# ADC.net
KiCad netlist of a schematic drawn in Altium Designer
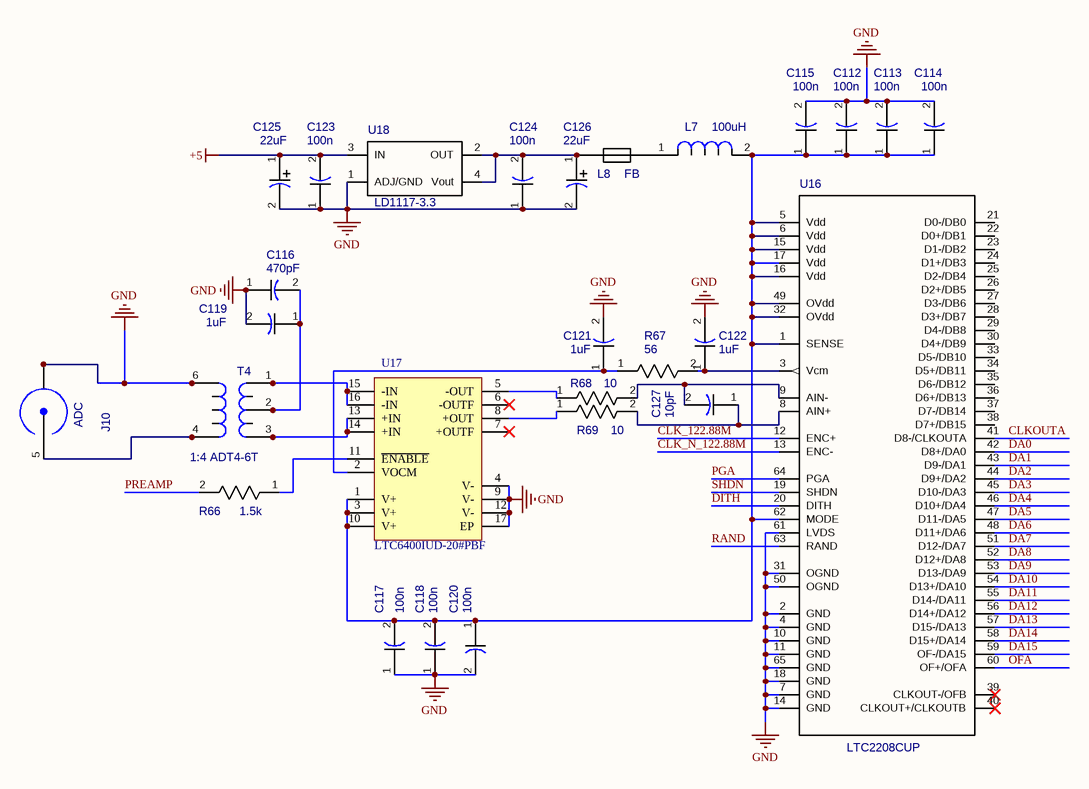
[diagram p0: ADC.SchDoc]

(export (version "E")
  (design (tool "Eeschema 10.0.6"))
  (components
    (comp (ref "C112")
      (value "100n")
      (footprint "CAP_0805")
      (description "CAP_0805")
      (libsource (lib "*") (part "CAP_0805"))
    )
    (comp (ref "C113")
      (value "100n")
      (footprint "CAP_0805")
      (description "CAP_0805")
      (libsource (lib "*") (part "CAP_0805"))
    )
    (comp (ref "C114")
      (value "100n")
      (footprint "CAP_0805")
      (description "CAP_0805")
      (libsource (lib "*") (part "CAP_0805"))
    )
    (comp (ref "C115")
      (value "100n")
      (footprint "CAP_0805")
      (description "CAP_0805")
      (libsource (lib "*") (part "CAP_0805"))
    )
    (comp (ref "C116")
      (value "470pF")
      (footprint "CAP_0805")
      (description "CAP_0805")
      (libsource (lib "*") (part "CAP_0805"))
    )
    (comp (ref "C117")
      (value "100n")
      (footprint "CAP_0805")
      (description "CAP_0805")
      (libsource (lib "*") (part "CAP_0805"))
    )
    (comp (ref "C118")
      (value "100n")
      (footprint "CAP_0805")
      (description "CAP_0805")
      (libsource (lib "*") (part "CAP_0805"))
    )
    (comp (ref "C119")
      (value "1uF")
      (footprint "CAP_0805")
      (description "CAP_0805")
      (libsource (lib "*") (part "CAP_0805"))
    )
    (comp (ref "C120")
      (value "100n")
      (footprint "CAP_0805")
      (description "CAP_0805")
      (libsource (lib "*") (part "CAP_0805"))
    )
    (comp (ref "C121")
      (value "1uF")
      (footprint "CAP_0805")
      (description "CAP_0805")
      (libsource (lib "*") (part "CAP_0805"))
    )
    (comp (ref "C122")
      (value "1uF")
      (footprint "CAP_0805")
      (description "CAP_0805")
      (libsource (lib "*") (part "CAP_0805"))
    )
    (comp (ref "C123")
      (value "100n")
      (footprint "CAP_0805")
      (description "CAP_0805")
      (libsource (lib "*") (part "CAP_0805"))
    )
    (comp (ref "C124")
      (value "100n")
      (footprint "CAP_0805")
      (description "CAP_0805")
      (libsource (lib "*") (part "CAP_0805"))
    )
    (comp (ref "C125") (value "22uF") (footprint "TC3528-1411") (libsource (lib "*") (part "EEEFC_sizeB")))
    (comp (ref "C126")
      (value "22uF")
      (footprint "TC3528-1411")
      (description "EEEFC_sizeB")
      (libsource (lib "*") (part "EEEFC_sizeB"))
    )
    (comp (ref "C127")
      (value "10pF")
      (footprint "CAP_0805")
      (description "CAP_0805")
      (libsource (lib "*") (part "CAP_0805"))
    )
    (comp (ref "J10")
      (value "ADC")
      (footprint "31-5431")
      (description "31-5431")
      (libsource (lib "RF-UNIT_1") (part "31-5431"))
    )
    (comp (ref "L7")
      (value "100uH")
      (footprint "14-1210")
      (description "IND_1206")
      (libsource (lib "*") (part "IND_1206"))
    )
    (comp (ref "L8")
      (value "FB")
      (footprint "IND_FERRITE_BEAD")
      (description "Ferrite bead on conductor")
      (libsource (lib "MOTHERBOARD_1") (part "IND_FERRITE_BEAD"))
    )
    (comp (ref "R66")
      (value "1.5k")
      (footprint "RES_0805")
      (description "RES_0805")
      (libsource (lib "*") (part "RES_0805"))
    )
    (comp (ref "R67")
      (value "56")
      (footprint "RES_0805")
      (description "RES_0805")
      (libsource (lib "") (part "RES_0805_1"))
    )
    (comp (ref "R68")
      (value "10")
      (footprint "RES_0603")
      (description "RES_0603")
      (libsource (lib "*") (part "RES_0603"))
    )
    (comp (ref "R69")
      (value "10")
      (footprint "RES_0603")
      (description "RES_0603")
      (libsource (lib "*") (part "RES_0603"))
    )
    (comp (ref "T4")
      (value "1:4 ADT4-6T")
      (footprint "TRANSF_ACORE2")
      (description "Transformer")
      (libsource (lib "MOTHERBOARD_1") (part "TRANSF_ACORE2"))
    )
    (comp (ref "U16") (value "LTC2208CUP") (footprint "LTC2208CUP") (libsource (lib "*") (part "LTC2208CUP")))
    (comp (ref "U17")
      (value "LTC6400IUD-20#PBF")
      (footprint "LT-UD-16_N")
      (fields
        (field (name "MANUFACTURER") "Linear Technology")
        (field (name "LINEAR TECHNOLOGY PART NUMBER") "LTC6400-20")
      )
      (libsource (lib "Altium Content Vault") (part "LT-LTC640X-X-16"))
    )
    (comp (ref "U18")
      (value "LD1117-3.3")
      (footprint "LT1117CST-3.3")
      (description "LT1117CST-3.3")
      (libsource (lib "*") (part "LT1117CST-3.3"))
    )
  )
  (nets
    (net (code "1") (name "+5") (class "Default")
      (node (ref "C123") (pin "2") (pinfunction "2_2") (pintype "passive"))
      (node (ref "C125") (pin "1") (pinfunction "PLUS_1") (pintype "passive"))
      (node (ref "U18") (pin "3") (pinfunction "IN_3") (pintype "passive"))
    )
    (net (code "2") (name "/CLKOUTA") (class "Default")
      (node (ref "U16") (pin "41") (pinfunction "D8-/CLKOUTA_41") (pintype "passive"))
    )
    (net (code "3") (name "/CLK_122.88M") (class "Default")
      (node (ref "U16") (pin "12") (pinfunction "ENC+_12") (pintype "passive"))
    )
    (net (code "4") (name "/CLK_N_122.88M") (class "Default")
      (node (ref "U16") (pin "13") (pinfunction "ENC-_13") (pintype "passive"))
    )
    (net (code "5") (name "/DA0") (class "Default")
      (node (ref "U16") (pin "42") (pinfunction "D8+/DA0_42") (pintype "passive"))
    )
    (net (code "6") (name "/DA1") (class "Default")
      (node (ref "U16") (pin "43") (pinfunction "D9-/DA1_43") (pintype "passive"))
    )
    (net (code "7") (name "/DA2") (class "Default")
      (node (ref "U16") (pin "44") (pinfunction "D9+/DA2_44") (pintype "passive"))
    )
    (net (code "8") (name "/DA3") (class "Default")
      (node (ref "U16") (pin "45") (pinfunction "D10-/DA3_45") (pintype "passive"))
    )
    (net (code "9") (name "/DA4") (class "Default")
      (node (ref "U16") (pin "46") (pinfunction "D10+/DA4_46") (pintype "passive"))
    )
    (net (code "10") (name "/DA5") (class "Default")
      (node (ref "U16") (pin "47") (pinfunction "D11-/DA5_47") (pintype "passive"))
    )
    (net (code "11") (name "/DA6") (class "Default")
      (node (ref "U16") (pin "48") (pinfunction "D11+/DA6_48") (pintype "passive"))
    )
    (net (code "12") (name "/DA7") (class "Default")
      (node (ref "U16") (pin "51") (pinfunction "D12-/DA7_51") (pintype "passive"))
    )
    (net (code "13") (name "/DA8") (class "Default")
      (node (ref "U16") (pin "52") (pinfunction "D12+/DA8_52") (pintype "passive"))
    )
    (net (code "14") (name "/DA9") (class "Default")
      (node (ref "U16") (pin "53") (pinfunction "D13-/DA9_53") (pintype "passive"))
    )
    (net (code "15") (name "/DA10") (class "Default")
      (node (ref "U16") (pin "54") (pinfunction "D13+/DA10_54") (pintype "passive"))
    )
    (net (code "16") (name "/DA11") (class "Default")
      (node (ref "U16") (pin "55") (pinfunction "D14-/DA11_55") (pintype "passive"))
    )
    (net (code "17") (name "/DA12") (class "Default")
      (node (ref "U16") (pin "56") (pinfunction "D14+/DA12_56") (pintype "passive"))
    )
    (net (code "18") (name "/DA13") (class "Default")
      (node (ref "U16") (pin "57") (pinfunction "D15-/DA13_57") (pintype "passive"))
    )
    (net (code "19") (name "/DA14") (class "Default")
      (node (ref "U16") (pin "58") (pinfunction "D15+/DA14_58") (pintype "passive"))
    )
    (net (code "20") (name "/DA15") (class "Default")
      (node (ref "U16") (pin "59") (pinfunction "OF-/DA15_59") (pintype "passive"))
    )
    (net (code "21") (name "/DITH") (class "Default")
      (node (ref "U16") (pin "20") (pinfunction "DITH_20") (pintype "passive"))
    )
    (net (code "22") (name "/OFA") (class "Default")
      (node (ref "U16") (pin "60") (pinfunction "OF+/OFA_60") (pintype "passive"))
    )
    (net (code "23") (name "/PGA") (class "Default")
      (node (ref "U16") (pin "64") (pinfunction "PGA_64") (pintype "passive"))
    )
    (net (code "24") (name "/PREAMP") (class "Default")
      (node (ref "R66") (pin "2") (pinfunction "1_2") (pintype "passive"))
    )
    (net (code "25") (name "/RAND") (class "Default")
      (node (ref "U16") (pin "63") (pinfunction "RAND_63") (pintype "passive"))
    )
    (net (code "26") (name "/SHDN") (class "Default")
      (node (ref "U16") (pin "19") (pinfunction "SHDN_19") (pintype "passive"))
    )
    (net (code "27") (name "GND") (class "Default")
      (node (ref "C112") (pin "2") (pinfunction "2_2") (pintype "passive"))
      (node (ref "C113") (pin "2") (pinfunction "2_2") (pintype "passive"))
      (node (ref "C114") (pin "2") (pinfunction "2_2") (pintype "passive"))
      (node (ref "C115") (pin "2") (pinfunction "2_2") (pintype "passive"))
      (node (ref "C116") (pin "1") (pinfunction "1_1") (pintype "passive"))
      (node (ref "C117") (pin "1") (pinfunction "1_1") (pintype "passive"))
      (node (ref "C118") (pin "1") (pinfunction "1_1") (pintype "passive"))
      (node (ref "C119") (pin "2") (pinfunction "2_2") (pintype "passive"))
      (node (ref "C120") (pin "2") (pinfunction "2_2") (pintype "passive"))
      (node (ref "C121") (pin "2") (pinfunction "2_2") (pintype "passive"))
      (node (ref "C122") (pin "2") (pinfunction "2_2") (pintype "passive"))
      (node (ref "C123") (pin "1") (pinfunction "1_1") (pintype "passive"))
      (node (ref "C124") (pin "1") (pinfunction "1_1") (pintype "passive"))
      (node (ref "C125") (pin "2") (pinfunction "MINUS_2") (pintype "passive"))
      (node (ref "C126") (pin "2") (pinfunction "MINUS_2") (pintype "passive"))
      (node (ref "J10") (pin "1") (pinfunction "GND_1") (pintype "passive"))
      (node (ref "J10") (pin "2") (pinfunction "GND_2") (pintype "passive"))
      (node (ref "J10") (pin "3") (pinfunction "GND_3") (pintype "passive"))
      (node (ref "J10") (pin "4") (pinfunction "GND_4") (pintype "passive"))
      (node (ref "T4") (pin "10") (pinfunction "0_10") (pintype "passive"))
      (node (ref "T4") (pin "6") (pinfunction "P2_6") (pintype "passive"))
      (node (ref "U16") (pin "10") (pinfunction "GND_10") (pintype "passive"))
      (node (ref "U16") (pin "11") (pinfunction "GND_11") (pintype "passive"))
      (node (ref "U16") (pin "14") (pinfunction "GND_14") (pintype "passive"))
      (node (ref "U16") (pin "18") (pinfunction "GND_18") (pintype "passive"))
      (node (ref "U16") (pin "2") (pinfunction "GND_2") (pintype "passive"))
      (node (ref "U16") (pin "31") (pinfunction "OGND_31") (pintype "passive"))
      (node (ref "U16") (pin "4") (pinfunction "GND_4") (pintype "passive"))
      (node (ref "U16") (pin "50") (pinfunction "OGND_50") (pintype "passive"))
      (node (ref "U16") (pin "61") (pinfunction "LVDS_61") (pintype "passive"))
      (node (ref "U16") (pin "65") (pinfunction "GND_65") (pintype "passive"))
      (node (ref "U16") (pin "7") (pinfunction "GND_7") (pintype "passive"))
      (node (ref "U17") (pin "12") (pinfunction "V-_12") (pintype "power_in"))
      (node (ref "U17") (pin "17") (pinfunction "EP_17") (pintype "power_in"))
      (node (ref "U17") (pin "4") (pinfunction "V-_4") (pintype "power_in"))
      (node (ref "U17") (pin "9") (pinfunction "V-_9") (pintype "power_in"))
      (node (ref "U18") (pin "1") (pinfunction "ADJ/GND_1") (pintype "passive"))
    )
    (net (code "28") (name "Net-(C126-PLUS)") (class "Default")
      (node (ref "C124") (pin "2") (pinfunction "2_2") (pintype "passive"))
      (node (ref "C126") (pin "1") (pinfunction "PLUS_1") (pintype "passive"))
      (node (ref "L8") (pin "1") (pinfunction "1_1") (pintype "passive"))
      (node (ref "U18") (pin "2") (pinfunction "OUT_2") (pintype "passive"))
      (node (ref "U18") (pin "4") (pinfunction "Vout_4") (pintype "passive"))
    )
    (net (code "29") (name "Net-(J10-CON)") (class "Default")
      (node (ref "J10") (pin "5") (pinfunction "CON_5") (pintype "passive"))
      (node (ref "T4") (pin "11") (pinfunction "0_11") (pintype "passive"))
      (node (ref "T4") (pin "4") (pinfunction "P1_4") (pintype "passive"))
    )
    (net (code "30") (name "Net-(L7-Pad1)") (class "Default")
      (node (ref "L7") (pin "1") (pinfunction "1_1") (pintype "passive"))
      (node (ref "L8") (pin "2") (pinfunction "2_2") (pintype "passive"))
    )
    (net (code "31") (name "Net-(R66-2)") (class "Default")
      (node (ref "R66") (pin "1") (pinfunction "2_1") (pintype "passive"))
      (node (ref "U17") (pin "11") (pinfunction "~{ENABLE}_11") (pintype "passive"))
    )
    (net (code "32") (name "Net-(T4-S1)") (class "Default")
      (node (ref "T4") (pin "3") (pinfunction "S1_3") (pintype "passive"))
      (node (ref "T4") (pin "9") (pinfunction "0_9") (pintype "passive"))
      (node (ref "U17") (pin "13") (pinfunction "+IN_13") (pintype "passive"))
      (node (ref "U17") (pin "14") (pinfunction "+IN_14") (pintype "passive"))
    )
    (net (code "33") (name "Net-(T4-S2)") (class "Default")
      (node (ref "C116") (pin "2") (pinfunction "2_2") (pintype "passive"))
      (node (ref "C119") (pin "1") (pinfunction "1_1") (pintype "passive"))
      (node (ref "T4") (pin "2") (pinfunction "S2_2") (pintype "passive"))
      (node (ref "T4") (pin "8") (pinfunction "0_8") (pintype "passive"))
    )
    (net (code "34") (name "Net-(T4-S3)") (class "Default")
      (node (ref "T4") (pin "1") (pinfunction "S3_1") (pintype "passive"))
      (node (ref "T4") (pin "7") (pinfunction "0_7") (pintype "passive"))
      (node (ref "U17") (pin "15") (pinfunction "-IN_15") (pintype "passive"))
      (node (ref "U17") (pin "16") (pinfunction "-IN_16") (pintype "passive"))
    )
    (net (code "35") (name "Net-(U16-AIN+)") (class "Default")
      (node (ref "C127") (pin "1") (pinfunction "1_1") (pintype "passive"))
      (node (ref "R69") (pin "2") (pinfunction "2_2") (pintype "passive"))
      (node (ref "U16") (pin "8") (pinfunction "AIN+_8") (pintype "passive"))
    )
    (net (code "36") (name "Net-(U16-AIN-)") (class "Default")
      (node (ref "C127") (pin "2") (pinfunction "2_2") (pintype "passive"))
      (node (ref "R68") (pin "2") (pinfunction "2_2") (pintype "passive"))
      (node (ref "U16") (pin "9") (pinfunction "AIN-_9") (pintype "passive"))
    )
    (net (code "37") (name "Net-(U16-MODE)") (class "Default")
      (node (ref "C112") (pin "1") (pinfunction "1_1") (pintype "passive"))
      (node (ref "C113") (pin "1") (pinfunction "1_1") (pintype "passive"))
      (node (ref "C114") (pin "1") (pinfunction "1_1") (pintype "passive"))
      (node (ref "C115") (pin "1") (pinfunction "1_1") (pintype "passive"))
      (node (ref "C117") (pin "2") (pinfunction "2_2") (pintype "passive"))
      (node (ref "C118") (pin "2") (pinfunction "2_2") (pintype "passive"))
      (node (ref "C120") (pin "1") (pinfunction "1_1") (pintype "passive"))
      (node (ref "L7") (pin "2") (pinfunction "2_2") (pintype "passive"))
      (node (ref "U16") (pin "1") (pinfunction "SENSE_1") (pintype "passive"))
      (node (ref "U16") (pin "15") (pinfunction "Vdd_15") (pintype "passive"))
      (node (ref "U16") (pin "16") (pinfunction "Vdd_16") (pintype "passive"))
      (node (ref "U16") (pin "17") (pinfunction "Vdd_17") (pintype "passive"))
      (node (ref "U16") (pin "32") (pinfunction "OVdd_32") (pintype "passive"))
      (node (ref "U16") (pin "49") (pinfunction "OVdd_49") (pintype "passive"))
      (node (ref "U16") (pin "5") (pinfunction "Vdd_5") (pintype "passive"))
      (node (ref "U16") (pin "6") (pinfunction "Vdd_6") (pintype "passive"))
      (node (ref "U16") (pin "62") (pinfunction "MODE_62") (pintype "passive"))
      (node (ref "U17") (pin "1") (pinfunction "V+_1") (pintype "power_in"))
      (node (ref "U17") (pin "10") (pinfunction "V+_10") (pintype "power_in"))
      (node (ref "U17") (pin "3") (pinfunction "V+_3") (pintype "power_in"))
    )
    (net (code "38") (name "Net-(U16-Vcm)") (class "Default")
      (node (ref "C122") (pin "1") (pinfunction "1_1") (pintype "passive"))
      (node (ref "R67") (pin "2") (pinfunction "2_2") (pintype "passive"))
      (node (ref "U16") (pin "3") (pinfunction "Vcm_3") (pintype "output"))
    )
    (net (code "39") (name "Net-(U17-+OUT)") (class "Default")
      (node (ref "R69") (pin "1") (pinfunction "1_1") (pintype "passive"))
      (node (ref "U17") (pin "8") (pinfunction "+OUT_8") (pintype "passive"))
    )
    (net (code "40") (name "Net-(U17--OUT)") (class "Default")
      (node (ref "R68") (pin "1") (pinfunction "1_1") (pintype "passive"))
      (node (ref "U17") (pin "5") (pinfunction "-OUT_5") (pintype "passive"))
    )
    (net (code "41") (name "Net-(U17-VOCM)") (class "Default")
      (node (ref "C121") (pin "1") (pinfunction "1_1") (pintype "passive"))
      (node (ref "R67") (pin "1") (pinfunction "1_1") (pintype "passive"))
      (node (ref "U17") (pin "2") (pinfunction "VOCM_2") (pintype "passive"))
    )
    (net (code "42") (name "unconnected-(U16-CLKOUT+{slash}CLKOUTB-Pad40)") (class "Default")
      (node (ref "U16") (pin "40") (pinfunction "CLKOUT+/CLKOUTB_40") (pintype "passive+no_connect"))
    )
    (net (code "43") (name "unconnected-(U16-CLKOUT-{slash}OFB-Pad39)") (class "Default")
      (node (ref "U16") (pin "39") (pinfunction "CLKOUT-/OFB_39") (pintype "passive+no_connect"))
    )
    (net (code "44") (name "unconnected-(U16-D0+{slash}DB1-Pad22)") (class "Default")
      (node (ref "U16") (pin "22") (pinfunction "D0+/DB1_22") (pintype "passive"))
    )
    (net (code "45") (name "unconnected-(U16-D0-{slash}DB0-Pad21)") (class "Default")
      (node (ref "U16") (pin "21") (pinfunction "D0-/DB0_21") (pintype "passive"))
    )
    (net (code "46") (name "unconnected-(U16-D1+{slash}DB3-Pad24)") (class "Default")
      (node (ref "U16") (pin "24") (pinfunction "D1+/DB3_24") (pintype "passive"))
    )
    (net (code "47") (name "unconnected-(U16-D1-{slash}DB2-Pad23)") (class "Default")
      (node (ref "U16") (pin "23") (pinfunction "D1-/DB2_23") (pintype "passive"))
    )
    (net (code "48") (name "unconnected-(U16-D2+{slash}DB5-Pad26)") (class "Default")
      (node (ref "U16") (pin "26") (pinfunction "D2+/DB5_26") (pintype "passive"))
    )
    (net (code "49") (name "unconnected-(U16-D2-{slash}DB4-Pad25)") (class "Default")
      (node (ref "U16") (pin "25") (pinfunction "D2-/DB4_25") (pintype "passive"))
    )
    (net (code "50") (name "unconnected-(U16-D3+{slash}DB7-Pad28)") (class "Default")
      (node (ref "U16") (pin "28") (pinfunction "D3+/DB7_28") (pintype "passive"))
    )
    (net (code "51") (name "unconnected-(U16-D3-{slash}DB6-Pad27)") (class "Default")
      (node (ref "U16") (pin "27") (pinfunction "D3-/DB6_27") (pintype "passive"))
    )
    (net (code "52") (name "unconnected-(U16-D4+{slash}DB9-Pad30)") (class "Default")
      (node (ref "U16") (pin "30") (pinfunction "D4+/DB9_30") (pintype "passive"))
    )
    (net (code "53") (name "unconnected-(U16-D4-{slash}DB8-Pad29)") (class "Default")
      (node (ref "U16") (pin "29") (pinfunction "D4-/DB8_29") (pintype "passive"))
    )
    (net (code "54") (name "unconnected-(U16-D5+{slash}DB11-Pad34)") (class "Default")
      (node (ref "U16") (pin "34") (pinfunction "D5+/DB11_34") (pintype "passive"))
    )
    (net (code "55") (name "unconnected-(U16-D5-{slash}DB10-Pad33)") (class "Default")
      (node (ref "U16") (pin "33") (pinfunction "D5-/DB10_33") (pintype "passive"))
    )
    (net (code "56") (name "unconnected-(U16-D6+{slash}DB13-Pad36)") (class "Default")
      (node (ref "U16") (pin "36") (pinfunction "D6+/DB13_36") (pintype "passive"))
    )
    (net (code "57") (name "unconnected-(U16-D6-{slash}DB12-Pad35)") (class "Default")
      (node (ref "U16") (pin "35") (pinfunction "D6-/DB12_35") (pintype "passive"))
    )
    (net (code "58") (name "unconnected-(U16-D7+{slash}DB15-Pad38)") (class "Default")
      (node (ref "U16") (pin "38") (pinfunction "D7+/DB15_38") (pintype "passive"))
    )
    (net (code "59") (name "unconnected-(U16-D7-{slash}DB14-Pad37)") (class "Default")
      (node (ref "U16") (pin "37") (pinfunction "D7-/DB14_37") (pintype "passive"))
    )
    (net (code "60") (name "unconnected-(U17-+OUTF-Pad7)") (class "Default")
      (node (ref "U17") (pin "7") (pinfunction "+OUTF_7") (pintype "passive+no_connect"))
    )
    (net (code "61") (name "unconnected-(U17--OUTF-Pad6)") (class "Default")
      (node (ref "U17") (pin "6") (pinfunction "-OUTF_6") (pintype "passive+no_connect"))
    )
  )
)
